# FPGA_POWER.net
KiCad netlist of a schematic drawn in Altium Designer
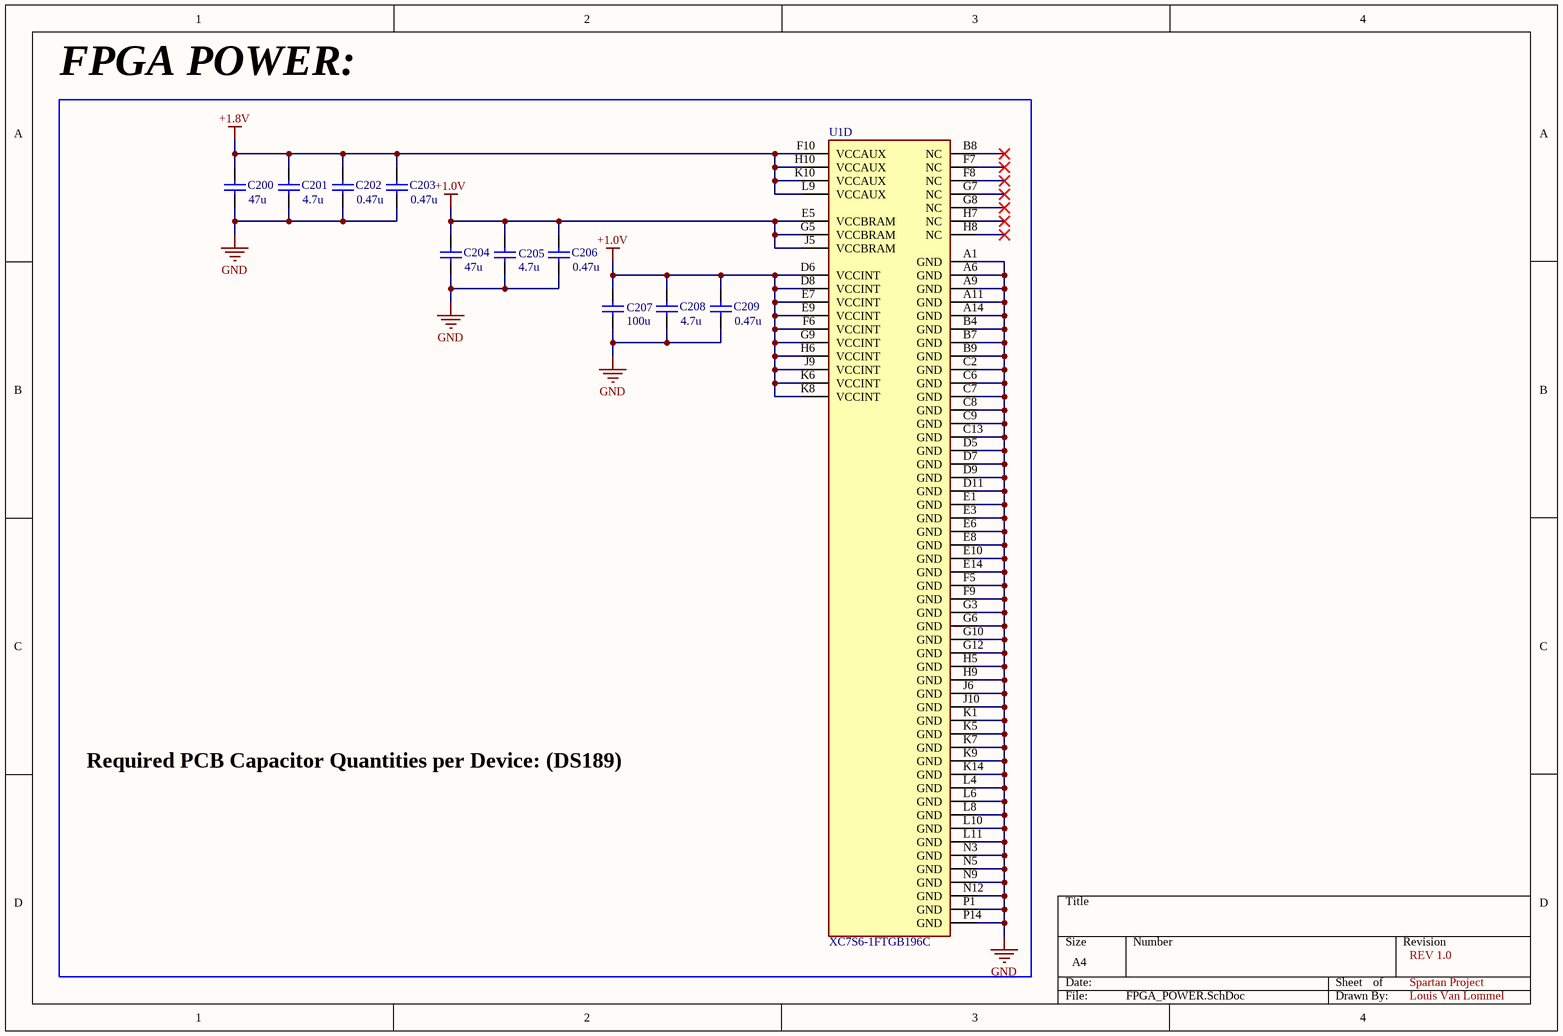
[diagram p0: FPGA_POWER.SchDoc]

(export (version "E")
  (design (tool "Eeschema 10.0.6"))
  (components
    (comp (ref "C200")
      (value "47u")
      (footprint "CAP_0603")
      (description "Capacitor")
      (fields (field (name "Comment") "47uF") (field (name "PUBLISHER") "Altium Limited"))
      (libsource (lib "Miscellaneous Devices") (part "Cap"))
    )
    (comp (ref "C201")
      (value "4.7u")
      (footprint "CAP_0402")
      (description "Capacitor")
      (fields (field (name "PUBLISHER") "Altium Limited"))
      (libsource (lib "Miscellaneous Devices") (part "Cap"))
    )
    (comp (ref "C202")
      (value "0.47u")
      (footprint "CAP_0402")
      (description "Capacitor")
      (fields (field (name "Comment") "0.47uF") (field (name "PUBLISHER") "Altium Limited"))
      (libsource (lib "Miscellaneous Devices") (part "Cap"))
    )
    (comp (ref "C203")
      (value "0.47u")
      (footprint "CAP_0402")
      (description "Capacitor")
      (fields (field (name "Comment") "0.47uF") (field (name "PUBLISHER") "Altium Limited"))
      (libsource (lib "Miscellaneous Devices") (part "Cap"))
    )
    (comp (ref "C204")
      (value "47u")
      (footprint "CAP_0603")
      (description "Capacitor")
      (fields (field (name "Comment") "47uF") (field (name "PUBLISHER") "Altium Limited"))
      (libsource (lib "Miscellaneous Devices") (part "Cap"))
    )
    (comp (ref "C205")
      (value "4.7u")
      (footprint "CAP_0402")
      (description "Capacitor")
      (fields (field (name "PUBLISHER") "Altium Limited"))
      (libsource (lib "Miscellaneous Devices") (part "Cap"))
    )
    (comp (ref "C206")
      (value "0.47u")
      (footprint "CAP_0402")
      (description "Capacitor")
      (fields (field (name "Comment") "0.47uF") (field (name "PUBLISHER") "Altium Limited"))
      (libsource (lib "Miscellaneous Devices") (part "Cap"))
    )
    (comp (ref "C207")
      (value "100u")
      (footprint "CAP_0805")
      (description "Capacitor")
      (fields (field (name "Comment") "100uF") (field (name "PUBLISHER") "Altium Limited"))
      (libsource (lib "Miscellaneous Devices") (part "Cap"))
    )
    (comp (ref "C208")
      (value "4.7u")
      (footprint "CAP_0402")
      (description "Capacitor")
      (fields (field (name "PUBLISHER") "Altium Limited"))
      (libsource (lib "Miscellaneous Devices") (part "Cap"))
    )
    (comp (ref "C209")
      (value "0.47u")
      (footprint "CAP_0402")
      (description "Capacitor")
      (fields (field (name "Comment") "0.47uF") (field (name "PUBLISHER") "Altium Limited"))
      (libsource (lib "Miscellaneous Devices") (part "Cap"))
    )
    (comp (ref "U1")
      (value "XC7S6-1FTGB196C")
      (footprint "FP-XC7S6-1FTGB196C-MFG")
      (fields
        (field (name "MANUFACTURER") "Xilinx")
        (field (name "OCTOPART") "https://octopart.com/xc7s6-1ftgb196c-xilinx-81890684")
      )
      (libsource (lib "Altium Content Vault") (part "4382e9425a5ef0cb43184b1739abe55"))
    )
  )
  (nets
    (net (code "1") (name "+1.0V") (class "Default")
      (node (ref "C204") (pin "2") (pinfunction "2_2") (pintype "passive"))
      (node (ref "C205") (pin "2") (pinfunction "2_2") (pintype "passive"))
      (node (ref "C206") (pin "2") (pinfunction "2_2") (pintype "passive"))
      (node (ref "C207") (pin "2") (pinfunction "2_2") (pintype "passive"))
      (node (ref "C208") (pin "2") (pinfunction "2_2") (pintype "passive"))
      (node (ref "C209") (pin "2") (pinfunction "2_2") (pintype "passive"))
      (node (ref "U1") (pin "D6") (pinfunction "VCCINT_D6") (pintype "passive"))
      (node (ref "U1") (pin "D8") (pinfunction "VCCINT_D8") (pintype "passive"))
      (node (ref "U1") (pin "E5") (pinfunction "VCCBRAM_E5") (pintype "passive"))
      (node (ref "U1") (pin "E7") (pinfunction "VCCINT_E7") (pintype "passive"))
      (node (ref "U1") (pin "E9") (pinfunction "VCCINT_E9") (pintype "passive"))
      (node (ref "U1") (pin "F6") (pinfunction "VCCINT_F6") (pintype "passive"))
      (node (ref "U1") (pin "G5") (pinfunction "VCCBRAM_G5") (pintype "passive"))
      (node (ref "U1") (pin "G9") (pinfunction "VCCINT_G9") (pintype "passive"))
      (node (ref "U1") (pin "H6") (pinfunction "VCCINT_H6") (pintype "passive"))
      (node (ref "U1") (pin "J5") (pinfunction "VCCBRAM_J5") (pintype "passive"))
      (node (ref "U1") (pin "J9") (pinfunction "VCCINT_J9") (pintype "passive"))
      (node (ref "U1") (pin "K6") (pinfunction "VCCINT_K6") (pintype "passive"))
      (node (ref "U1") (pin "K8") (pinfunction "VCCINT_K8") (pintype "passive"))
    )
    (net (code "2") (name "+1.8V") (class "Default")
      (node (ref "C200") (pin "2") (pinfunction "2_2") (pintype "passive"))
      (node (ref "C201") (pin "2") (pinfunction "2_2") (pintype "passive"))
      (node (ref "C202") (pin "2") (pinfunction "2_2") (pintype "passive"))
      (node (ref "C203") (pin "2") (pinfunction "2_2") (pintype "passive"))
      (node (ref "U1") (pin "F10") (pinfunction "VCCAUX_F10") (pintype "passive"))
      (node (ref "U1") (pin "H10") (pinfunction "VCCAUX_H10") (pintype "passive"))
      (node (ref "U1") (pin "K10") (pinfunction "VCCAUX_K10") (pintype "passive"))
      (node (ref "U1") (pin "L9") (pinfunction "VCCAUX_L9") (pintype "passive"))
    )
    (net (code "3") (name "GND") (class "Default")
      (node (ref "C200") (pin "1") (pinfunction "1_1") (pintype "passive"))
      (node (ref "C201") (pin "1") (pinfunction "1_1") (pintype "passive"))
      (node (ref "C202") (pin "1") (pinfunction "1_1") (pintype "passive"))
      (node (ref "C203") (pin "1") (pinfunction "1_1") (pintype "passive"))
      (node (ref "C204") (pin "1") (pinfunction "1_1") (pintype "passive"))
      (node (ref "C205") (pin "1") (pinfunction "1_1") (pintype "passive"))
      (node (ref "C206") (pin "1") (pinfunction "1_1") (pintype "passive"))
      (node (ref "C207") (pin "1") (pinfunction "1_1") (pintype "passive"))
      (node (ref "C208") (pin "1") (pinfunction "1_1") (pintype "passive"))
      (node (ref "C209") (pin "1") (pinfunction "1_1") (pintype "passive"))
      (node (ref "U1") (pin "A1") (pinfunction "GND_A1") (pintype "passive"))
      (node (ref "U1") (pin "A11") (pinfunction "GND_A11") (pintype "passive"))
      (node (ref "U1") (pin "A14") (pinfunction "GND_A14") (pintype "passive"))
      (node (ref "U1") (pin "A6") (pinfunction "GND_A6") (pintype "passive"))
      (node (ref "U1") (pin "A9") (pinfunction "GND_A9") (pintype "passive"))
      (node (ref "U1") (pin "B4") (pinfunction "GND_B4") (pintype "passive"))
      (node (ref "U1") (pin "B7") (pinfunction "GND_B7") (pintype "passive"))
      (node (ref "U1") (pin "B9") (pinfunction "GND_B9") (pintype "passive"))
      (node (ref "U1") (pin "C13") (pinfunction "GND_C13") (pintype "passive"))
      (node (ref "U1") (pin "C2") (pinfunction "GND_C2") (pintype "passive"))
      (node (ref "U1") (pin "C6") (pinfunction "GND_C6") (pintype "passive"))
      (node (ref "U1") (pin "C7") (pinfunction "GND_C7") (pintype "passive"))
      (node (ref "U1") (pin "C8") (pinfunction "GND_C8") (pintype "passive"))
      (node (ref "U1") (pin "C9") (pinfunction "GND_C9") (pintype "passive"))
      (node (ref "U1") (pin "D11") (pinfunction "GND_D11") (pintype "passive"))
      (node (ref "U1") (pin "D5") (pinfunction "GND_D5") (pintype "passive"))
      (node (ref "U1") (pin "D7") (pinfunction "GND_D7") (pintype "passive"))
      (node (ref "U1") (pin "D9") (pinfunction "GND_D9") (pintype "passive"))
      (node (ref "U1") (pin "E1") (pinfunction "GND_E1") (pintype "passive"))
      (node (ref "U1") (pin "E10") (pinfunction "GND_E10") (pintype "passive"))
      (node (ref "U1") (pin "E14") (pinfunction "GND_E14") (pintype "passive"))
      (node (ref "U1") (pin "E3") (pinfunction "GND_E3") (pintype "passive"))
      (node (ref "U1") (pin "E6") (pinfunction "GND_E6") (pintype "passive"))
      (node (ref "U1") (pin "E8") (pinfunction "GND_E8") (pintype "passive"))
      (node (ref "U1") (pin "F5") (pinfunction "GND_F5") (pintype "passive"))
      (node (ref "U1") (pin "F9") (pinfunction "GND_F9") (pintype "passive"))
      (node (ref "U1") (pin "G10") (pinfunction "GND_G10") (pintype "passive"))
      (node (ref "U1") (pin "G12") (pinfunction "GND_G12") (pintype "passive"))
      (node (ref "U1") (pin "G3") (pinfunction "GND_G3") (pintype "passive"))
      (node (ref "U1") (pin "G6") (pinfunction "GND_G6") (pintype "passive"))
      (node (ref "U1") (pin "H5") (pinfunction "GND_H5") (pintype "passive"))
      (node (ref "U1") (pin "H9") (pinfunction "GND_H9") (pintype "passive"))
      (node (ref "U1") (pin "J10") (pinfunction "GND_J10") (pintype "passive"))
      (node (ref "U1") (pin "J6") (pinfunction "GND_J6") (pintype "passive"))
      (node (ref "U1") (pin "K1") (pinfunction "GND_K1") (pintype "passive"))
      (node (ref "U1") (pin "K14") (pinfunction "GND_K14") (pintype "passive"))
      (node (ref "U1") (pin "K5") (pinfunction "GND_K5") (pintype "passive"))
      (node (ref "U1") (pin "K7") (pinfunction "GND_K7") (pintype "passive"))
      (node (ref "U1") (pin "K9") (pinfunction "GND_K9") (pintype "passive"))
      (node (ref "U1") (pin "L10") (pinfunction "GND_L10") (pintype "passive"))
      (node (ref "U1") (pin "L11") (pinfunction "GND_L11") (pintype "passive"))
      (node (ref "U1") (pin "L4") (pinfunction "GND_L4") (pintype "passive"))
      (node (ref "U1") (pin "L6") (pinfunction "GND_L6") (pintype "passive"))
      (node (ref "U1") (pin "L8") (pinfunction "GND_L8") (pintype "passive"))
      (node (ref "U1") (pin "N12") (pinfunction "GND_N12") (pintype "passive"))
      (node (ref "U1") (pin "N3") (pinfunction "GND_N3") (pintype "passive"))
      (node (ref "U1") (pin "N5") (pinfunction "GND_N5") (pintype "passive"))
      (node (ref "U1") (pin "N9") (pinfunction "GND_N9") (pintype "passive"))
      (node (ref "U1") (pin "P1") (pinfunction "GND_P1") (pintype "passive"))
      (node (ref "U1") (pin "P14") (pinfunction "GND_P14") (pintype "passive"))
    )
    (net (code "4") (name "unconnected-(U1D-NC-PadB8)") (class "Default")
      (node (ref "U1") (pin "B8") (pinfunction "NC_B8") (pintype "passive+no_connect"))
    )
    (net (code "5") (name "unconnected-(U1D-NC-PadF7)") (class "Default")
      (node (ref "U1") (pin "F7") (pinfunction "NC_F7") (pintype "passive+no_connect"))
    )
    (net (code "6") (name "unconnected-(U1D-NC-PadF8)") (class "Default")
      (node (ref "U1") (pin "F8") (pinfunction "NC_F8") (pintype "passive+no_connect"))
    )
    (net (code "7") (name "unconnected-(U1D-NC-PadG7)") (class "Default")
      (node (ref "U1") (pin "G7") (pinfunction "NC_G7") (pintype "passive+no_connect"))
    )
    (net (code "8") (name "unconnected-(U1D-NC-PadG8)") (class "Default")
      (node (ref "U1") (pin "G8") (pinfunction "NC_G8") (pintype "passive+no_connect"))
    )
    (net (code "9") (name "unconnected-(U1D-NC-PadH7)") (class "Default")
      (node (ref "U1") (pin "H7") (pinfunction "NC_H7") (pintype "passive+no_connect"))
    )
    (net (code "10") (name "unconnected-(U1D-NC-PadH8)") (class "Default")
      (node (ref "U1") (pin "H8") (pinfunction "NC_H8") (pintype "passive+no_connect"))
    )
  )
)
